# oscistack.net
KiCad netlist of a schematic drawn in Altium Designer
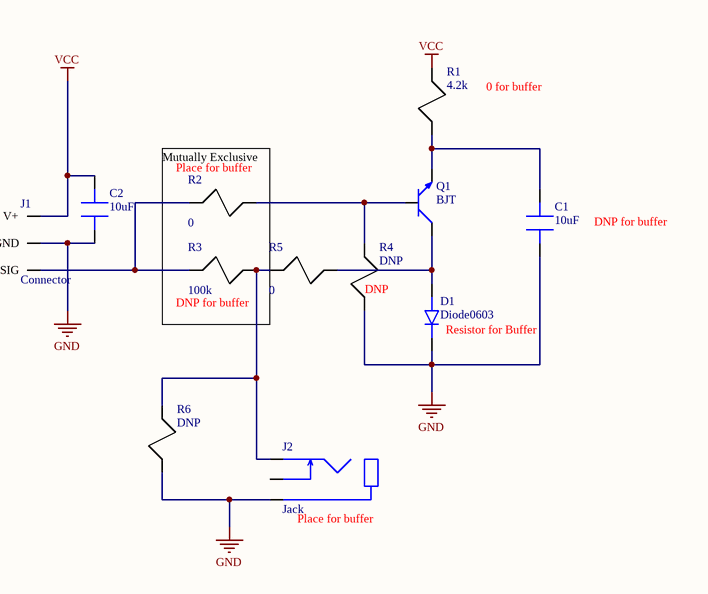
[diagram p0: oscistack.SchDoc]

(export (version "E")
  (design (tool "Eeschema 10.0.6"))
  (components
    (comp (ref "C1") (value "10uF") (footprint "Res0603") (libsource (lib "Components") (part "Cap0603")))
    (comp (ref "C2") (value "10uF") (footprint "Res0603") (libsource (lib "Components") (part "Cap0603")))
    (comp (ref "D1")
      (value "Diode0603")
      (footprint "LED0603")
      (libsource (lib "Components") (part "Diode0603"))
    )
    (comp (ref "J1")
      (value "Connector")
      (footprint "Header1x3")
      (libsource (lib "Components") (part "Connector"))
    )
    (comp (ref "J2") (value "Jack") (libsource (lib "Components") (part "Jack")))
    (comp (ref "Q1") (value "BJT") (footprint "BJT") (libsource (lib "Components") (part "BJT")))
    (comp (ref "R1") (value "4.2k") (footprint "Res0603") (libsource (lib "Components") (part "Res0603")))
    (comp (ref "R2") (value "0") (footprint "Res0603") (libsource (lib "Components") (part "Res0603")))
    (comp (ref "R3") (value "100k") (footprint "Res0603") (libsource (lib "Components") (part "Res0603")))
    (comp (ref "R4") (value "DNP") (footprint "Res0603") (libsource (lib "Components") (part "Res0603")))
    (comp (ref "R5") (value "0") (footprint "Res0603") (libsource (lib "Components") (part "Res0603")))
    (comp (ref "R6") (value "DNP") (footprint "Res0603") (libsource (lib "Components") (part "Res0603")))
  )
  (nets
    (net (code "1") (name "GND") (class "Default")
      (node (ref "C1") (pin "2") (pinfunction "2_2") (pintype "passive"))
      (node (ref "C2") (pin "2") (pinfunction "2_2") (pintype "passive"))
      (node (ref "D1") (pin "K") (pinfunction "K_K") (pintype "passive"))
      (node (ref "J1") (pin "GND") (pinfunction "GND_GND") (pintype "passive"))
      (node (ref "J2") (pin "S") (pinfunction "S_S") (pintype "passive"))
      (node (ref "R4") (pin "2") (pinfunction "2_2") (pintype "passive"))
      (node (ref "R6") (pin "2") (pinfunction "2_2") (pintype "passive"))
    )
    (net (code "2") (name "Net-(C1-Pad1)") (class "Default")
      (node (ref "C1") (pin "1") (pinfunction "1_1") (pintype "passive"))
      (node (ref "Q1") (pin "E") (pinfunction "E_E") (pintype "passive"))
      (node (ref "R1") (pin "2") (pinfunction "2_2") (pintype "passive"))
    )
    (net (code "3") (name "Net-(D1-PadA)") (class "Default")
      (node (ref "D1") (pin "A") (pinfunction "A_A") (pintype "passive"))
      (node (ref "Q1") (pin "C") (pinfunction "C_C") (pintype "passive"))
      (node (ref "R5") (pin "1") (pinfunction "1_1") (pintype "passive"))
    )
    (net (code "4") (name "Net-(J1-PadSIG)") (class "Default")
      (node (ref "J1") (pin "SIG") (pinfunction "SIG_SIG") (pintype "passive"))
      (node (ref "R2") (pin "1") (pinfunction "1_1") (pintype "passive"))
      (node (ref "R3") (pin "1") (pinfunction "1_1") (pintype "passive"))
    )
    (net (code "5") (name "Net-(J2-PadT)") (class "Default")
      (node (ref "J2") (pin "T") (pinfunction "T_T") (pintype "passive"))
      (node (ref "R3") (pin "2") (pinfunction "2_2") (pintype "passive"))
      (node (ref "R5") (pin "2") (pinfunction "2_2") (pintype "passive"))
      (node (ref "R6") (pin "1") (pinfunction "1_1") (pintype "passive"))
    )
    (net (code "6") (name "Net-(Q1-PadB)") (class "Default")
      (node (ref "Q1") (pin "B") (pinfunction "B_B") (pintype "passive"))
      (node (ref "R2") (pin "2") (pinfunction "2_2") (pintype "passive"))
      (node (ref "R4") (pin "1") (pinfunction "1_1") (pintype "passive"))
    )
    (net (code "7") (name "VCC") (class "Default")
      (node (ref "C2") (pin "1") (pinfunction "1_1") (pintype "passive"))
      (node (ref "J1") (pin "V+") (pinfunction "V+_V+") (pintype "passive"))
      (node (ref "R1") (pin "1") (pinfunction "1_1") (pintype "passive"))
    )
    (net (code "8") (name "unconnected-(J2-PadSW)") (class "Default")
      (node (ref "J2") (pin "SW") (pinfunction "SW_SW") (pintype "passive"))
    )
  )
)
